# System_Buttons.net
KiCad netlist of a schematic drawn in EAGLE
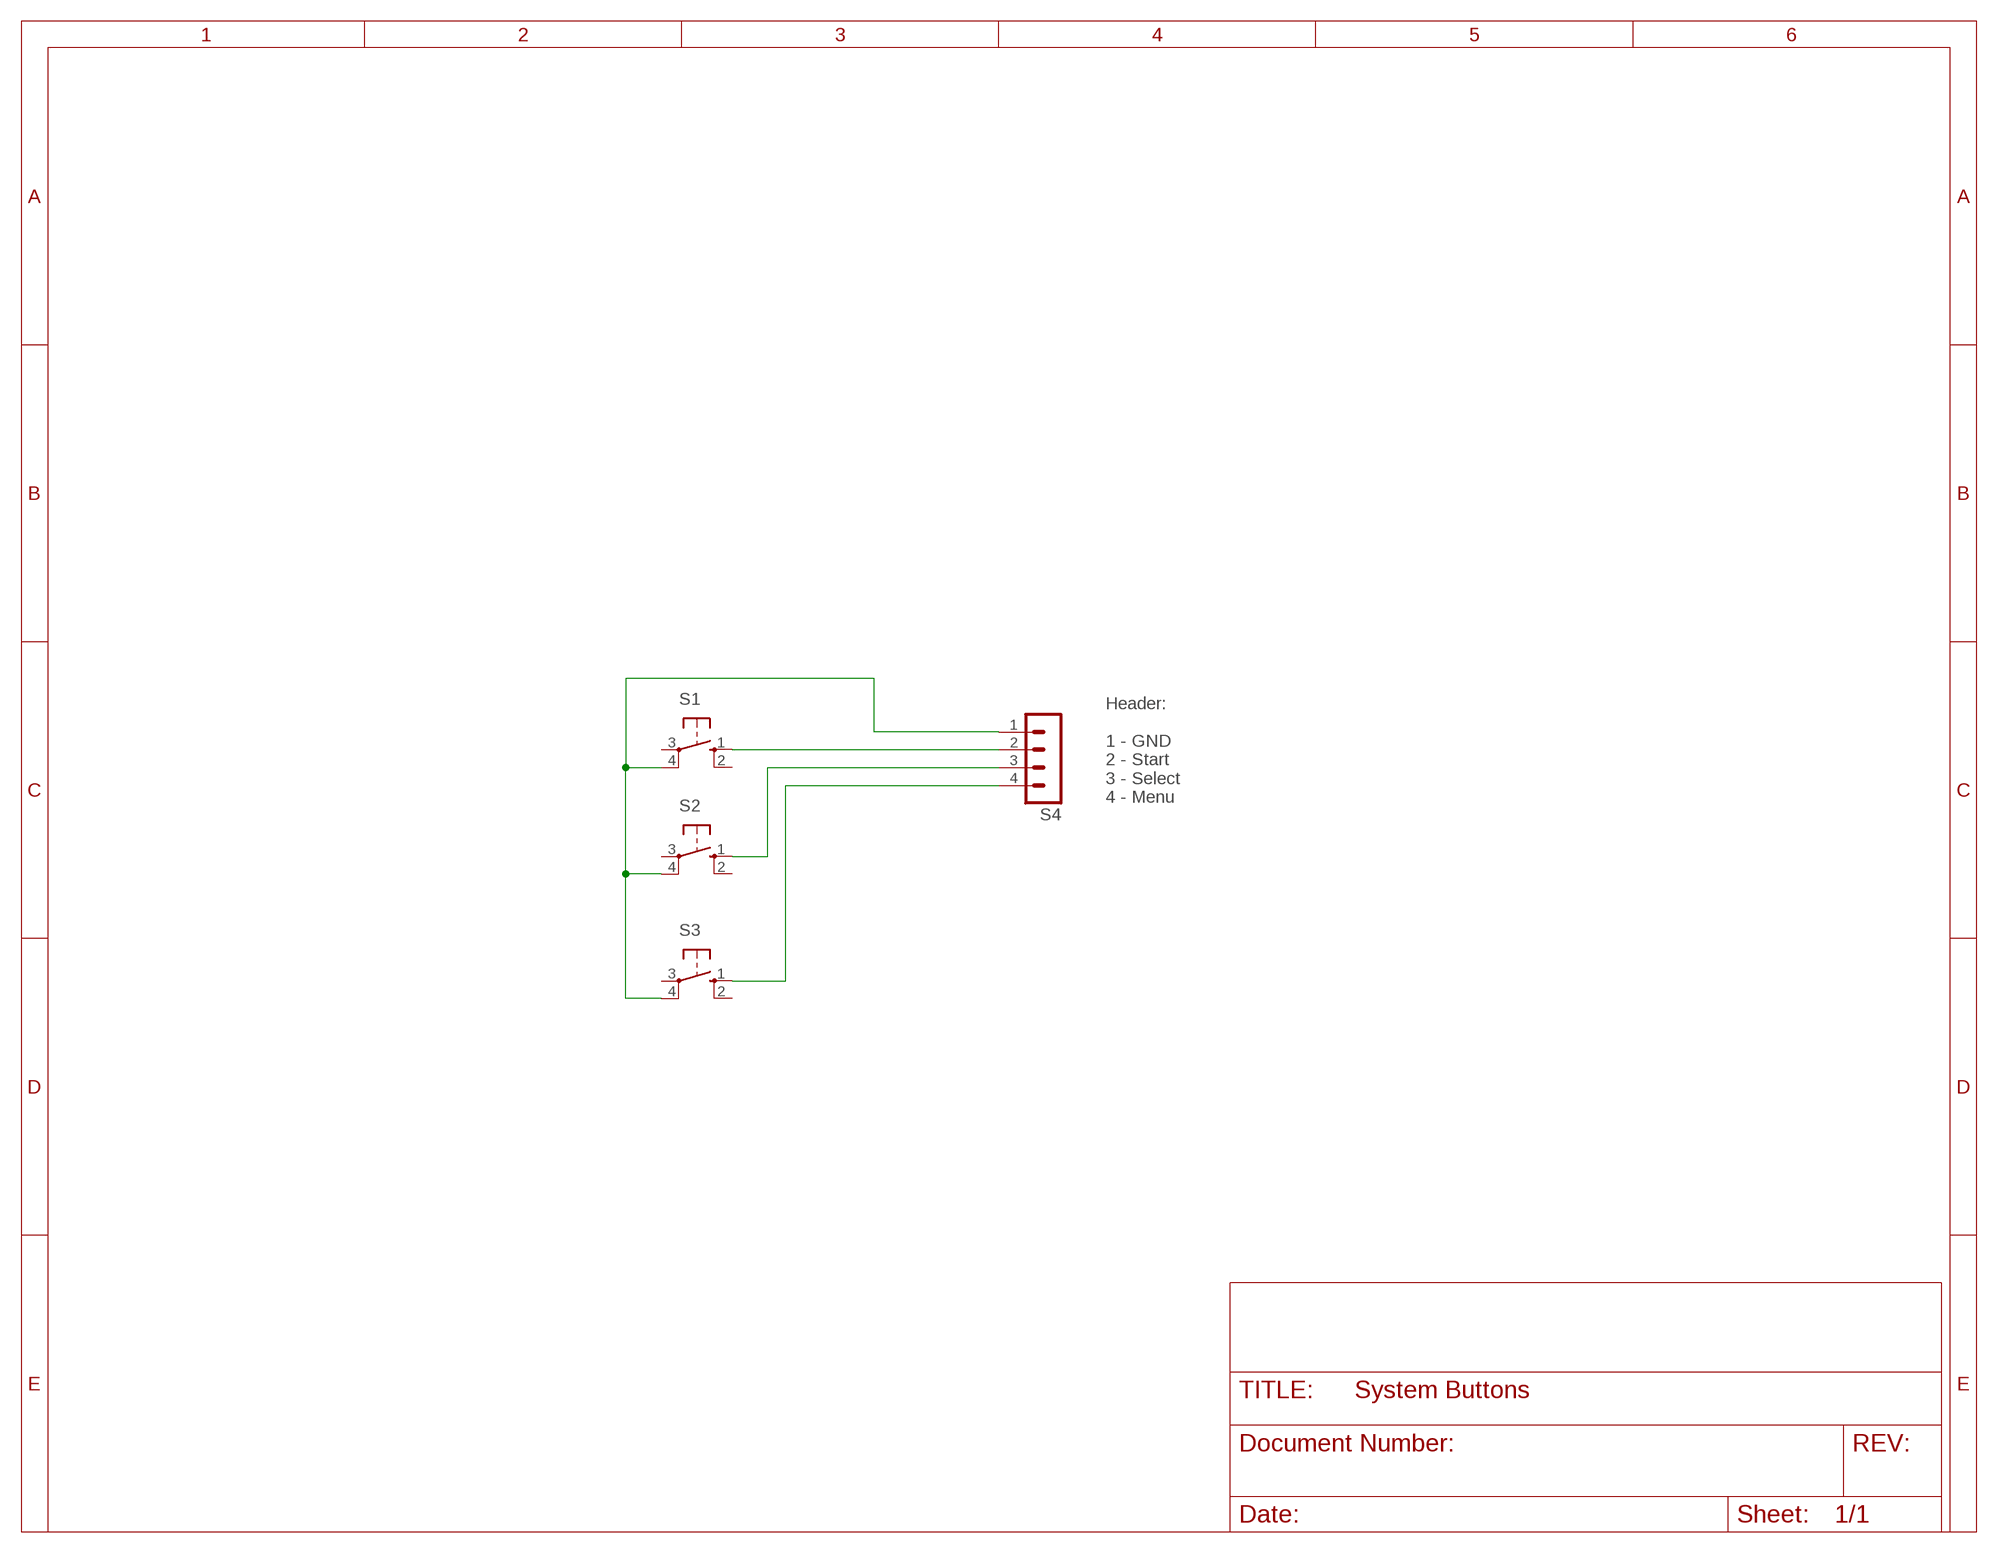
[diagram p0: schematic, sheet 1]

(export (version "E")
  (design (tool "Eeschema 10.0.6"))
  (components
    (comp (ref "S1")
      (value "10-XX")
      (footprint "eagle-import:B3F-10XX")
      (fields (field (name "MPN") "B3F-1000"))
      (libsource (lib "eagle-import") (part "10-XX"))
    )
    (comp (ref "S2")
      (value "10-XX")
      (footprint "eagle-import:B3F-10XX")
      (fields (field (name "MPN") "B3F-1000"))
      (libsource (lib "eagle-import") (part "10-XX"))
    )
    (comp (ref "S3")
      (value "10-XX")
      (footprint "eagle-import:B3F-10XX")
      (fields (field (name "MPN") "B3F-1000"))
      (libsource (lib "eagle-import") (part "10-XX"))
    )
    (comp (ref "S4")
      (value "MA04-1")
      (footprint "eagle-import:MA04-1")
      (libsource (lib "eagle-import") (part "MA04-1"))
    )
  )
  (nets
    (net (code "1") (name "Net-(S1-P1)") (class "Default")
      (node (ref "S1") (pin "4") (pinfunction "P1_4") (pintype "passive"))
      (node (ref "S2") (pin "4") (pinfunction "P1_4") (pintype "passive"))
      (node (ref "S3") (pin "4") (pinfunction "P1_4") (pintype "passive"))
      (node (ref "S4") (pin "1") (pinfunction "1_1") (pintype "passive"))
    )
    (net (code "2") (name "Net-(S1-S)") (class "Default")
      (node (ref "S1") (pin "1") (pinfunction "S_1") (pintype "passive"))
      (node (ref "S4") (pin "2") (pinfunction "2_2") (pintype "passive"))
    )
    (net (code "3") (name "Net-(S2-S)") (class "Default")
      (node (ref "S2") (pin "1") (pinfunction "S_1") (pintype "passive"))
      (node (ref "S4") (pin "3") (pinfunction "3_3") (pintype "passive"))
    )
    (net (code "4") (name "Net-(S3-S)") (class "Default")
      (node (ref "S3") (pin "1") (pinfunction "S_1") (pintype "passive"))
      (node (ref "S4") (pin "4") (pinfunction "4_4") (pintype "passive"))
    )
    (net (code "5") (name "unconnected-(S1-P-Pad3)") (class "Default")
      (node (ref "S1") (pin "3") (pinfunction "P_3") (pintype "passive"))
    )
    (net (code "6") (name "unconnected-(S1-S1-Pad2)") (class "Default")
      (node (ref "S1") (pin "2") (pinfunction "S1_2") (pintype "passive"))
    )
    (net (code "7") (name "unconnected-(S2-P-Pad3)") (class "Default")
      (node (ref "S2") (pin "3") (pinfunction "P_3") (pintype "passive"))
    )
    (net (code "8") (name "unconnected-(S2-S1-Pad2)") (class "Default")
      (node (ref "S2") (pin "2") (pinfunction "S1_2") (pintype "passive"))
    )
    (net (code "9") (name "unconnected-(S3-P-Pad3)") (class "Default")
      (node (ref "S3") (pin "3") (pinfunction "P_3") (pintype "passive"))
    )
    (net (code "10") (name "unconnected-(S3-S1-Pad2)") (class "Default")
      (node (ref "S3") (pin "2") (pinfunction "S1_2") (pintype "passive"))
    )
  )
)
